# pec.net
KiCad netlist of a schematic drawn in Altium Designer
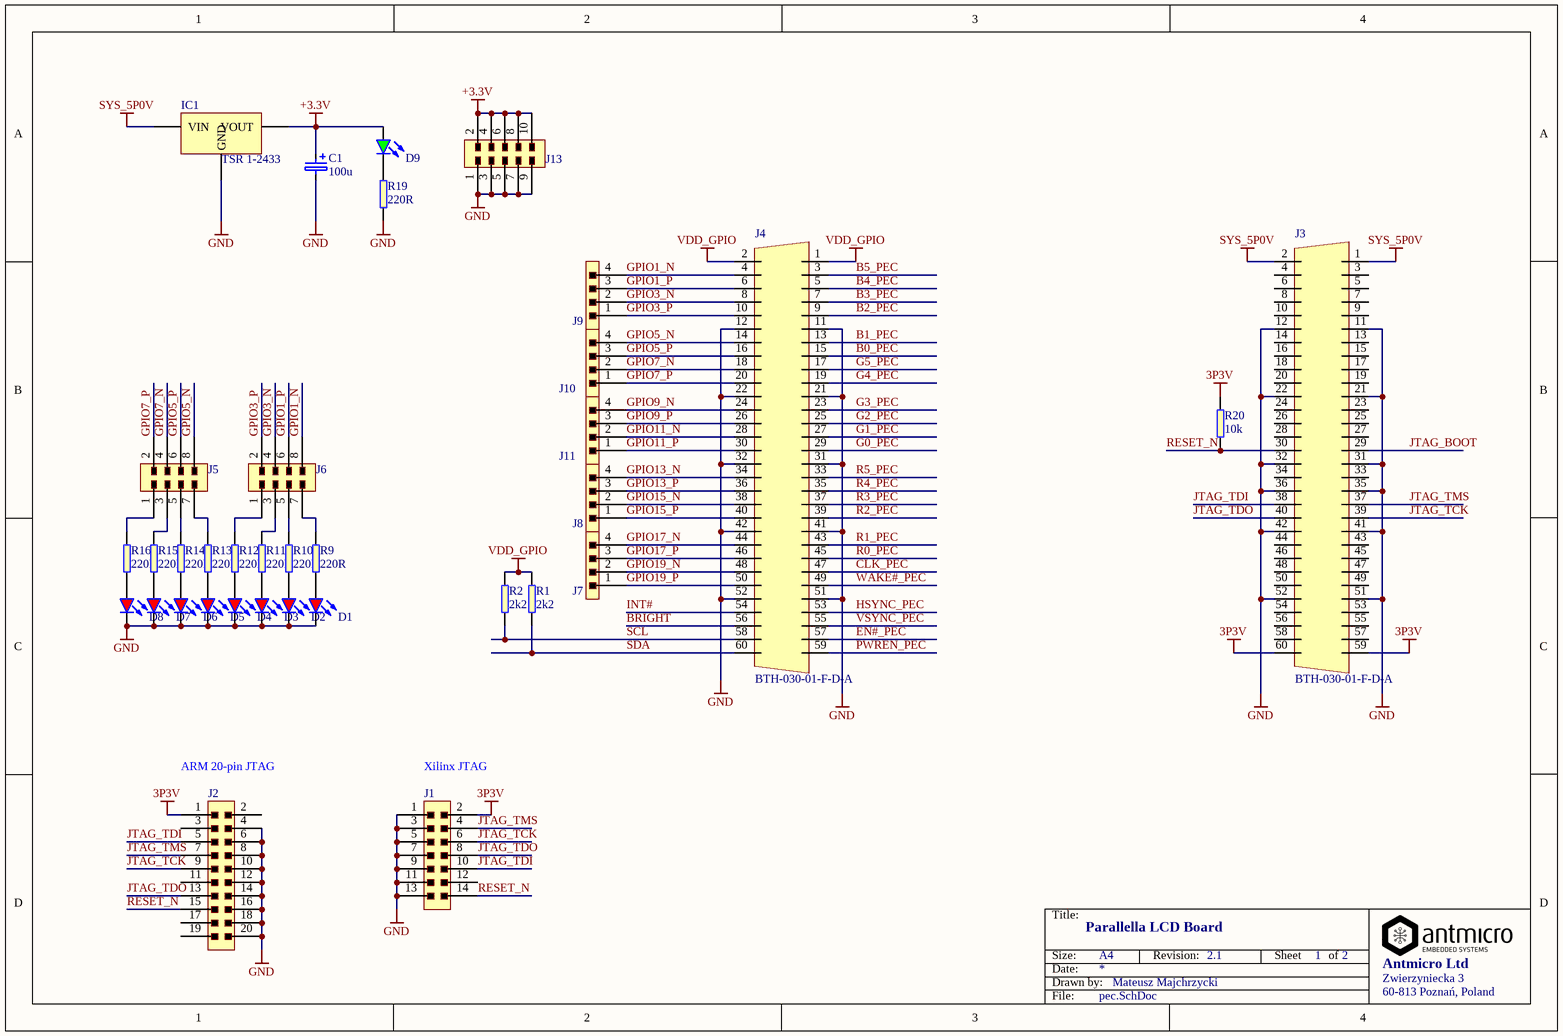
[diagram p0: pec.SchDoc]

(export (version "E")
  (design (tool "Eeschema 10.0.6"))
  (components
    (comp (ref "C1")
      (value "100u")
      (footprint "KEMET_C")
      (description "Tantalum SMT Capacitor 100uF Case KEMET_C")
      (fields (field (name "PART NUMBER") "C_100u_KEMET_C") (field (name "VOLTAGE") "10V"))
      (libsource (lib "AntmicroComponents") (part "CPol"))
    )
    (comp (ref "D1")
      (value "Red")
      (footprint "LED0603")
      (description "LED Red 0603 case")
      (fields (field (name "PART NUMBER") "LED_R"))
      (libsource (lib "AntmicroComponents") (part "LED"))
    )
    (comp (ref "D2")
      (value "Red")
      (footprint "LED0603")
      (description "LED Red 0603 case")
      (fields (field (name "PART NUMBER") "LED_R"))
      (libsource (lib "AntmicroComponents") (part "LED"))
    )
    (comp (ref "D3")
      (value "Red")
      (footprint "LED0603")
      (description "LED Red 0603 case")
      (fields (field (name "PART NUMBER") "LED_R"))
      (libsource (lib "AntmicroComponents") (part "LED"))
    )
    (comp (ref "D4")
      (value "Red")
      (footprint "LED0603")
      (description "LED Red 0603 case")
      (fields (field (name "PART NUMBER") "LED_R"))
      (libsource (lib "AntmicroComponents") (part "LED"))
    )
    (comp (ref "D5")
      (value "Red")
      (footprint "LED0603")
      (description "LED Red 0603 case")
      (fields (field (name "PART NUMBER") "LED_R"))
      (libsource (lib "AntmicroComponents") (part "LED"))
    )
    (comp (ref "D6")
      (value "Red")
      (footprint "LED0603")
      (description "LED Red 0603 case")
      (fields (field (name "PART NUMBER") "LED_R"))
      (libsource (lib "AntmicroComponents") (part "LED"))
    )
    (comp (ref "D7")
      (value "Red")
      (footprint "LED0603")
      (description "LED Red 0603 case")
      (fields (field (name "PART NUMBER") "LED_R"))
      (libsource (lib "AntmicroComponents") (part "LED"))
    )
    (comp (ref "D8")
      (value "Red")
      (footprint "LED0603")
      (description "LED Red 0603 case")
      (fields (field (name "PART NUMBER") "LED_R"))
      (libsource (lib "AntmicroComponents") (part "LED"))
    )
    (comp (ref "D9")
      (value "Green")
      (footprint "LED0603")
      (description "LED Green 0603 case")
      (fields (field (name "PART NUMBER") "LED_G"))
      (libsource (lib "AntmicroComponents") (part "LED"))
    )
    (comp (ref "IC1")
      (value "TSR 1-2433")
      (footprint "TSR1")
      (description "TRACOPOWER - TSR 1-2433 - CONVERTER, DC TO DC, 3.3V, 1A, SIP")
      (libsource (lib "AntmicroComponents") (part "VREG"))
    )
    (comp (ref "J1")
      (value "Molex-87831-1420")
      (footprint "87831-1420")
      (description "2x7 pinhead male")
      (libsource (lib "AntmicroComponents") (part "HEADER_2X7_male"))
    )
    (comp (ref "J2")
      (value "*")
      (footprint "HEADER_2X10_male 2.54mm")
      (description "2x10 pinhead male")
      (fields (field (name "PART NUMBER") "HEADER_2X10_male"))
      (libsource (lib "AntmicroComponents") (part "HEADER_2X10_male"))
    )
    (comp (ref "J3")
      (value "BTH-030-01-F-D-A")
      (footprint "BTH-030-01-F-D-A")
      (libsource (lib "AntmicroComponents") (part "BTH-030-01-F-D-A"))
    )
    (comp (ref "J4")
      (value "BTH-030-01-F-D-A")
      (footprint "BTH-030-01-F-D-A")
      (libsource (lib "AntmicroComponents") (part "BTH-030-01-F-D-A"))
    )
    (comp (ref "J5")
      (value "*")
      (footprint "HEADER_2X4_male 2mm")
      (description "2x4 pinhead male")
      (fields (field (name "PART NUMBER") "HEADER_2X4_male"))
      (libsource (lib "AntmicroComponents") (part "HEADER_2X4_male"))
    )
    (comp (ref "J6")
      (value "*")
      (footprint "HEADER_2X4_male 2mm")
      (description "2x4 pinhead male")
      (fields (field (name "PART NUMBER") "HEADER_2X4_male"))
      (libsource (lib "AntmicroComponents") (part "HEADER_2X4_male"))
    )
    (comp (ref "J7")
      (value "HEADER_1X4_male")
      (footprint "HEADER_1X4_male 2.54mm")
      (description "1x4 pinhead male")
      (libsource (lib "AntmicroComponents") (part "HEADER_1X4_male"))
    )
    (comp (ref "J8")
      (value "HEADER_1X4_male")
      (footprint "HEADER_1X4_male 2.54mm")
      (description "1x4 pinhead male")
      (libsource (lib "AntmicroComponents") (part "HEADER_1X4_male"))
    )
    (comp (ref "J9")
      (value "HEADER_1X4_male")
      (footprint "HEADER_1X4_male 2.54mm")
      (description "1x4 pinhead male")
      (libsource (lib "AntmicroComponents") (part "HEADER_1X4_male"))
    )
    (comp (ref "J10")
      (value "HEADER_1X4_male")
      (footprint "HEADER_1X4_male 2.54mm")
      (description "1x4 pinhead male")
      (libsource (lib "AntmicroComponents") (part "HEADER_1X4_male"))
    )
    (comp (ref "J11")
      (value "HEADER_1X4_male")
      (footprint "HEADER_1X4_male 2.54mm")
      (description "1x4 pinhead male")
      (libsource (lib "AntmicroComponents") (part "HEADER_1X4_male"))
    )
    (comp (ref "J13")
      (value "*")
      (footprint "HEADER_2X5_male 2.54mm")
      (description "2x5 pinhead male")
      (fields (field (name "PART NUMBER") "HEADER_2X5_male"))
      (libsource (lib "AntmicroComponents") (part "HEADER_2X5_male"))
    )
    (comp (ref "R1")
      (value "2k2")
      (footprint "0603")
      (description "SMT Resistor 2k2 0603")
      (fields (field (name "PART NUMBER") "R_2k2_0603"))
      (libsource (lib "") (part "R_1"))
    )
    (comp (ref "R2")
      (value "2k2")
      (footprint "0603")
      (description "SMT Resistor 2k2 0603")
      (fields (field (name "PART NUMBER") "R_2k2_0603"))
      (libsource (lib "") (part "R_1"))
    )
    (comp (ref "R9")
      (value "220R")
      (footprint "0603")
      (description "SMT Resistor 220R 0603")
      (fields (field (name "PART NUMBER") "R_220R_0603"))
      (libsource (lib "AntmicroComponents") (part "R"))
    )
    (comp (ref "R10")
      (value "220R")
      (footprint "0603")
      (description "SMT Resistor 220R 0603")
      (fields (field (name "PART NUMBER") "R_220R_0603"))
      (libsource (lib "AntmicroComponents") (part "R"))
    )
    (comp (ref "R11")
      (value "220R")
      (footprint "0603")
      (description "SMT Resistor 220R 0603")
      (fields (field (name "PART NUMBER") "R_220R_0603"))
      (libsource (lib "AntmicroComponents") (part "R"))
    )
    (comp (ref "R12")
      (value "220R")
      (footprint "0603")
      (description "SMT Resistor 220R 0603")
      (fields (field (name "PART NUMBER") "R_220R_0603"))
      (libsource (lib "AntmicroComponents") (part "R"))
    )
    (comp (ref "R13")
      (value "220R")
      (footprint "0603")
      (description "SMT Resistor 220R 0603")
      (fields (field (name "PART NUMBER") "R_220R_0603"))
      (libsource (lib "AntmicroComponents") (part "R"))
    )
    (comp (ref "R14")
      (value "220R")
      (footprint "0603")
      (description "SMT Resistor 220R 0603")
      (fields (field (name "PART NUMBER") "R_220R_0603"))
      (libsource (lib "AntmicroComponents") (part "R"))
    )
    (comp (ref "R15")
      (value "220R")
      (footprint "0603")
      (description "SMT Resistor 220R 0603")
      (fields (field (name "PART NUMBER") "R_220R_0603"))
      (libsource (lib "AntmicroComponents") (part "R"))
    )
    (comp (ref "R16")
      (value "220R")
      (footprint "0603")
      (description "SMT Resistor 220R 0603")
      (fields (field (name "PART NUMBER") "R_220R_0603"))
      (libsource (lib "AntmicroComponents") (part "R"))
    )
    (comp (ref "R19")
      (value "220R")
      (footprint "0603")
      (description "SMT Resistor 220R 0603")
      (fields (field (name "PART NUMBER") "R_220R_0603"))
      (libsource (lib "AntmicroComponents") (part "R"))
    )
    (comp (ref "R20")
      (value "10k")
      (footprint "0603")
      (description "SMT Resistor 10k 0603")
      (fields (field (name "PART NUMBER") "R_10k_0603"))
      (libsource (lib "AntmicroComponents") (part "R"))
    )
  )
  (nets
    (net (code "1") (name "+3.3V") (class "Default")
      (node (ref "C1") (pin "1") (pinfunction "1_1") (pintype "passive"))
      (node (ref "D9") (pin "A") (pinfunction "A_A") (pintype "passive"))
      (node (ref "IC1") (pin "3") (pinfunction "VOUT_3") (pintype "power_in"))
      (node (ref "J13") (pin "10") (pinfunction "10_10") (pintype "passive"))
      (node (ref "J13") (pin "2") (pinfunction "2_2") (pintype "passive"))
      (node (ref "J13") (pin "4") (pinfunction "4_4") (pintype "passive"))
      (node (ref "J13") (pin "6") (pinfunction "6_6") (pintype "passive"))
      (node (ref "J13") (pin "8") (pinfunction "8_8") (pintype "passive"))
    )
    (net (code "2") (name "/B0_PEC") (class "Default")
      (node (ref "J4") (pin "15") (pinfunction "15_15") (pintype "passive"))
    )
    (net (code "3") (name "/B1_PEC") (class "Default")
      (node (ref "J4") (pin "13") (pinfunction "13_13") (pintype "passive"))
    )
    (net (code "4") (name "/B2_PEC") (class "Default")
      (node (ref "J4") (pin "9") (pinfunction "9_9") (pintype "passive"))
    )
    (net (code "5") (name "/B3_PEC") (class "Default")
      (node (ref "J4") (pin "7") (pinfunction "7_7") (pintype "passive"))
    )
    (net (code "6") (name "/B4_PEC") (class "Default")
      (node (ref "J4") (pin "5") (pinfunction "5_5") (pintype "passive"))
    )
    (net (code "7") (name "/B5_PEC") (class "Default")
      (node (ref "J4") (pin "3") (pinfunction "3_3") (pintype "passive"))
    )
    (net (code "8") (name "/BRIGHT") (class "Default")
      (node (ref "J4") (pin "56") (pinfunction "56_56") (pintype "passive"))
    )
    (net (code "9") (name "/CLK_PEC") (class "Default")
      (node (ref "J4") (pin "47") (pinfunction "47_47") (pintype "passive"))
    )
    (net (code "10") (name "/EN#_PEC") (class "Default")
      (node (ref "J4") (pin "57") (pinfunction "57_57") (pintype "passive"))
    )
    (net (code "11") (name "/G0_PEC") (class "Default")
      (node (ref "J4") (pin "29") (pinfunction "29_29") (pintype "passive"))
    )
    (net (code "12") (name "/G1_PEC") (class "Default")
      (node (ref "J4") (pin "27") (pinfunction "27_27") (pintype "passive"))
    )
    (net (code "13") (name "/G2_PEC") (class "Default")
      (node (ref "J4") (pin "25") (pinfunction "25_25") (pintype "passive"))
    )
    (net (code "14") (name "/G3_PEC") (class "Default")
      (node (ref "J4") (pin "23") (pinfunction "23_23") (pintype "passive"))
    )
    (net (code "15") (name "/G4_PEC") (class "Default")
      (node (ref "J4") (pin "19") (pinfunction "19_19") (pintype "passive"))
    )
    (net (code "16") (name "/G5_PEC") (class "Default")
      (node (ref "J4") (pin "17") (pinfunction "17_17") (pintype "passive"))
    )
    (net (code "17") (name "/GPIO1_N") (class "Default")
      (node (ref "J4") (pin "4") (pinfunction "4_4") (pintype "passive"))
      (node (ref "J6") (pin "8") (pinfunction "8_8") (pintype "passive"))
      (node (ref "J9") (pin "4") (pinfunction "4_4") (pintype "passive"))
    )
    (net (code "18") (name "/GPIO1_P") (class "Default")
      (node (ref "J4") (pin "6") (pinfunction "6_6") (pintype "passive"))
      (node (ref "J6") (pin "6") (pinfunction "6_6") (pintype "passive"))
      (node (ref "J9") (pin "3") (pinfunction "3_3") (pintype "passive"))
    )
    (net (code "19") (name "/GPIO3_N") (class "Default")
      (node (ref "J4") (pin "8") (pinfunction "8_8") (pintype "passive"))
      (node (ref "J6") (pin "4") (pinfunction "4_4") (pintype "passive"))
      (node (ref "J9") (pin "2") (pinfunction "2_2") (pintype "passive"))
    )
    (net (code "20") (name "/GPIO3_P") (class "Default")
      (node (ref "J4") (pin "10") (pinfunction "10_10") (pintype "passive"))
      (node (ref "J6") (pin "2") (pinfunction "2_2") (pintype "passive"))
      (node (ref "J9") (pin "1") (pinfunction "1_1") (pintype "passive"))
    )
    (net (code "21") (name "/GPIO5_N") (class "Default")
      (node (ref "J10") (pin "4") (pinfunction "4_4") (pintype "passive"))
      (node (ref "J4") (pin "14") (pinfunction "14_14") (pintype "passive"))
      (node (ref "J5") (pin "8") (pinfunction "8_8") (pintype "passive"))
    )
    (net (code "22") (name "/GPIO5_P") (class "Default")
      (node (ref "J10") (pin "3") (pinfunction "3_3") (pintype "passive"))
      (node (ref "J4") (pin "16") (pinfunction "16_16") (pintype "passive"))
      (node (ref "J5") (pin "6") (pinfunction "6_6") (pintype "passive"))
    )
    (net (code "23") (name "/GPIO7_N") (class "Default")
      (node (ref "J10") (pin "2") (pinfunction "2_2") (pintype "passive"))
      (node (ref "J4") (pin "18") (pinfunction "18_18") (pintype "passive"))
      (node (ref "J5") (pin "4") (pinfunction "4_4") (pintype "passive"))
    )
    (net (code "24") (name "/GPIO7_P") (class "Default")
      (node (ref "J10") (pin "1") (pinfunction "1_1") (pintype "passive"))
      (node (ref "J4") (pin "20") (pinfunction "20_20") (pintype "passive"))
      (node (ref "J5") (pin "2") (pinfunction "2_2") (pintype "passive"))
    )
    (net (code "25") (name "/GPIO9_N") (class "Default")
      (node (ref "J11") (pin "4") (pinfunction "4_4") (pintype "passive"))
      (node (ref "J4") (pin "24") (pinfunction "24_24") (pintype "passive"))
    )
    (net (code "26") (name "/GPIO9_P") (class "Default")
      (node (ref "J11") (pin "3") (pinfunction "3_3") (pintype "passive"))
      (node (ref "J4") (pin "26") (pinfunction "26_26") (pintype "passive"))
    )
    (net (code "27") (name "/GPIO11_N") (class "Default")
      (node (ref "J11") (pin "2") (pinfunction "2_2") (pintype "passive"))
      (node (ref "J4") (pin "28") (pinfunction "28_28") (pintype "passive"))
    )
    (net (code "28") (name "/GPIO11_P") (class "Default")
      (node (ref "J11") (pin "1") (pinfunction "1_1") (pintype "passive"))
      (node (ref "J4") (pin "30") (pinfunction "30_30") (pintype "passive"))
    )
    (net (code "29") (name "/GPIO13_N") (class "Default")
      (node (ref "J4") (pin "34") (pinfunction "34_34") (pintype "passive"))
      (node (ref "J8") (pin "4") (pinfunction "4_4") (pintype "passive"))
    )
    (net (code "30") (name "/GPIO13_P") (class "Default")
      (node (ref "J4") (pin "36") (pinfunction "36_36") (pintype "passive"))
      (node (ref "J8") (pin "3") (pinfunction "3_3") (pintype "passive"))
    )
    (net (code "31") (name "/GPIO15_N") (class "Default")
      (node (ref "J4") (pin "38") (pinfunction "38_38") (pintype "passive"))
      (node (ref "J8") (pin "2") (pinfunction "2_2") (pintype "passive"))
    )
    (net (code "32") (name "/GPIO15_P") (class "Default")
      (node (ref "J4") (pin "40") (pinfunction "40_40") (pintype "passive"))
      (node (ref "J8") (pin "1") (pinfunction "1_1") (pintype "passive"))
    )
    (net (code "33") (name "/GPIO17_N") (class "Default")
      (node (ref "J4") (pin "44") (pinfunction "44_44") (pintype "passive"))
      (node (ref "J7") (pin "4") (pinfunction "4_4") (pintype "passive"))
    )
    (net (code "34") (name "/GPIO17_P") (class "Default")
      (node (ref "J4") (pin "46") (pinfunction "46_46") (pintype "passive"))
      (node (ref "J7") (pin "3") (pinfunction "3_3") (pintype "passive"))
    )
    (net (code "35") (name "/GPIO19_N") (class "Default")
      (node (ref "J4") (pin "48") (pinfunction "48_48") (pintype "passive"))
      (node (ref "J7") (pin "2") (pinfunction "2_2") (pintype "passive"))
    )
    (net (code "36") (name "/GPIO19_P") (class "Default")
      (node (ref "J4") (pin "50") (pinfunction "50_50") (pintype "passive"))
      (node (ref "J7") (pin "1") (pinfunction "1_1") (pintype "passive"))
    )
    (net (code "37") (name "/HSYNC_PEC") (class "Default")
      (node (ref "J4") (pin "53") (pinfunction "53_53") (pintype "passive"))
    )
    (net (code "38") (name "/INT#") (class "Default")
      (node (ref "J4") (pin "54") (pinfunction "54_54") (pintype "passive"))
    )
    (net (code "39") (name "/JTAG_BOOT") (class "Default")
      (node (ref "J3") (pin "29") (pinfunction "29_29") (pintype "passive"))
    )
    (net (code "40") (name "/JTAG_TCK") (class "Default")
      (node (ref "J1") (pin "6") (pinfunction "6_6") (pintype "passive"))
      (node (ref "J2") (pin "9") (pinfunction "9_9") (pintype "passive"))
      (node (ref "J3") (pin "39") (pinfunction "39_39") (pintype "passive"))
    )
    (net (code "41") (name "/JTAG_TDI") (class "Default")
      (node (ref "J1") (pin "10") (pinfunction "10_10") (pintype "passive"))
      (node (ref "J2") (pin "5") (pinfunction "5_5") (pintype "passive"))
      (node (ref "J3") (pin "38") (pinfunction "38_38") (pintype "passive"))
    )
    (net (code "42") (name "/JTAG_TDO") (class "Default")
      (node (ref "J1") (pin "8") (pinfunction "8_8") (pintype "passive"))
      (node (ref "J2") (pin "13") (pinfunction "13_13") (pintype "passive"))
      (node (ref "J3") (pin "40") (pinfunction "40_40") (pintype "passive"))
    )
    (net (code "43") (name "/JTAG_TMS") (class "Default")
      (node (ref "J1") (pin "4") (pinfunction "4_4") (pintype "passive"))
      (node (ref "J2") (pin "7") (pinfunction "7_7") (pintype "passive"))
      (node (ref "J3") (pin "37") (pinfunction "37_37") (pintype "passive"))
    )
    (net (code "44") (name "/PWREN_PEC") (class "Default")
      (node (ref "J4") (pin "59") (pinfunction "59_59") (pintype "passive"))
    )
    (net (code "45") (name "/R0_PEC") (class "Default")
      (node (ref "J4") (pin "45") (pinfunction "45_45") (pintype "passive"))
    )
    (net (code "46") (name "/R1_PEC") (class "Default")
      (node (ref "J4") (pin "43") (pinfunction "43_43") (pintype "passive"))
    )
    (net (code "47") (name "/R2_PEC") (class "Default")
      (node (ref "J4") (pin "39") (pinfunction "39_39") (pintype "passive"))
    )
    (net (code "48") (name "/R3_PEC") (class "Default")
      (node (ref "J4") (pin "37") (pinfunction "37_37") (pintype "passive"))
    )
    (net (code "49") (name "/R4_PEC") (class "Default")
      (node (ref "J4") (pin "35") (pinfunction "35_35") (pintype "passive"))
    )
    (net (code "50") (name "/R5_PEC") (class "Default")
      (node (ref "J4") (pin "33") (pinfunction "33_33") (pintype "passive"))
    )
    (net (code "51") (name "/RESET_N") (class "Default")
      (node (ref "J1") (pin "14") (pinfunction "14_14") (pintype "passive"))
      (node (ref "J2") (pin "15") (pinfunction "15_15") (pintype "passive"))
      (node (ref "J3") (pin "30") (pinfunction "30_30") (pintype "passive"))
      (node (ref "R20") (pin "1") (pintype "passive"))
    )
    (net (code "52") (name "/SCL") (class "Default")
      (node (ref "J4") (pin "58") (pinfunction "58_58") (pintype "passive"))
      (node (ref "R2") (pin "1") (pintype "passive"))
    )
    (net (code "53") (name "/SDA") (class "Default")
      (node (ref "J4") (pin "60") (pinfunction "60_60") (pintype "passive"))
      (node (ref "R1") (pin "1") (pintype "passive"))
    )
    (net (code "54") (name "/VSYNC_PEC") (class "Default")
      (node (ref "J4") (pin "55") (pinfunction "55_55") (pintype "passive"))
    )
    (net (code "55") (name "/WAKE#_PEC") (class "Default")
      (node (ref "J4") (pin "49") (pinfunction "49_49") (pintype "passive"))
    )
    (net (code "56") (name "3P3V") (class "Default")
      (node (ref "J1") (pin "2") (pinfunction "2_2") (pintype "passive"))
      (node (ref "J2") (pin "1") (pinfunction "1_1") (pintype "passive"))
      (node (ref "J3") (pin "59") (pinfunction "59_59") (pintype "passive"))
      (node (ref "J3") (pin "60") (pinfunction "60_60") (pintype "passive"))
      (node (ref "R20") (pin "2") (pintype "passive"))
    )
    (net (code "57") (name "GND") (class "Default")
      (node (ref "C1") (pin "2") (pinfunction "2_2") (pintype "passive"))
      (node (ref "D1") (pin "K") (pinfunction "K_K") (pintype "passive"))
      (node (ref "D2") (pin "K") (pinfunction "K_K") (pintype "passive"))
      (node (ref "D3") (pin "K") (pinfunction "K_K") (pintype "passive"))
      (node (ref "D4") (pin "K") (pinfunction "K_K") (pintype "passive"))
      (node (ref "D5") (pin "K") (pinfunction "K_K") (pintype "passive"))
      (node (ref "D6") (pin "K") (pinfunction "K_K") (pintype "passive"))
      (node (ref "D7") (pin "K") (pinfunction "K_K") (pintype "passive"))
      (node (ref "D8") (pin "K") (pinfunction "K_K") (pintype "passive"))
      (node (ref "IC1") (pin "2") (pinfunction "GND_2") (pintype "power_in"))
      (node (ref "J1") (pin "1") (pinfunction "1_1") (pintype "passive"))
      (node (ref "J1") (pin "11") (pinfunction "11_11") (pintype "passive"))
      (node (ref "J1") (pin "13") (pinfunction "13_13") (pintype "passive"))
      (node (ref "J1") (pin "3") (pinfunction "3_3") (pintype "passive"))
      (node (ref "J1") (pin "5") (pinfunction "5_5") (pintype "passive"))
      (node (ref "J1") (pin "7") (pinfunction "7_7") (pintype "passive"))
      (node (ref "J1") (pin "9") (pinfunction "9_9") (pintype "passive"))
      (node (ref "J13") (pin "1") (pinfunction "1_1") (pintype "passive"))
      (node (ref "J13") (pin "3") (pinfunction "3_3") (pintype "passive"))
      (node (ref "J13") (pin "5") (pinfunction "5_5") (pintype "passive"))
      (node (ref "J13") (pin "7") (pinfunction "7_7") (pintype "passive"))
      (node (ref "J13") (pin "9") (pinfunction "9_9") (pintype "passive"))
      (node (ref "J2") (pin "10") (pinfunction "10_10") (pintype "passive"))
      (node (ref "J2") (pin "12") (pinfunction "12_12") (pintype "passive"))
      (node (ref "J2") (pin "14") (pinfunction "14_14") (pintype "passive"))
      (node (ref "J2") (pin "16") (pinfunction "16_16") (pintype "passive"))
      (node (ref "J2") (pin "18") (pinfunction "18_18") (pintype "passive"))
      (node (ref "J2") (pin "20") (pinfunction "20_20") (pintype "passive"))
      (node (ref "J2") (pin "4") (pinfunction "4_4") (pintype "passive"))
      (node (ref "J2") (pin "6") (pinfunction "6_6") (pintype "passive"))
      (node (ref "J2") (pin "8") (pinfunction "8_8") (pintype "passive"))
      (node (ref "J3") (pin "11") (pinfunction "11_11") (pintype "passive"))
      (node (ref "J3") (pin "12") (pinfunction "12_12") (pintype "passive"))
      (node (ref "J3") (pin "21") (pinfunction "21_21") (pintype "passive"))
      (node (ref "J3") (pin "22") (pinfunction "22_22") (pintype "passive"))
      (node (ref "J3") (pin "31") (pinfunction "31_31") (pintype "passive"))
      (node (ref "J3") (pin "32") (pinfunction "32_32") (pintype "passive"))
      (node (ref "J3") (pin "35") (pinfunction "35_35") (pintype "passive"))
      (node (ref "J3") (pin "36") (pinfunction "36_36") (pintype "passive"))
      (node (ref "J3") (pin "41") (pinfunction "41_41") (pintype "passive"))
      (node (ref "J3") (pin "42") (pinfunction "42_42") (pintype "passive"))
      (node (ref "J3") (pin "51") (pinfunction "51_51") (pintype "passive"))
      (node (ref "J3") (pin "52") (pinfunction "52_52") (pintype "passive"))
      (node (ref "J4") (pin "11") (pinfunction "11_11") (pintype "passive"))
      (node (ref "J4") (pin "12") (pinfunction "12_12") (pintype "passive"))
      (node (ref "J4") (pin "21") (pinfunction "21_21") (pintype "passive"))
      (node (ref "J4") (pin "22") (pinfunction "22_22") (pintype "passive"))
      (node (ref "J4") (pin "31") (pinfunction "31_31") (pintype "passive"))
      (node (ref "J4") (pin "32") (pinfunction "32_32") (pintype "passive"))
      (node (ref "J4") (pin "41") (pinfunction "41_41") (pintype "passive"))
      (node (ref "J4") (pin "42") (pinfunction "42_42") (pintype "passive"))
      (node (ref "J4") (pin "51") (pinfunction "51_51") (pintype "passive"))
      (node (ref "J4") (pin "52") (pinfunction "52_52") (pintype "passive"))
      (node (ref "R19") (pin "1") (pintype "passive"))
    )
    (net (code "58") (name "Net-(D1-PadA)") (class "Default")
      (node (ref "D1") (pin "A") (pinfunction "A_A") (pintype "passive"))
      (node (ref "R9") (pin "1") (pintype "passive"))
    )
    (net (code "59") (name "Net-(D2-PadA)") (class "Default")
      (node (ref "D2") (pin "A") (pinfunction "A_A") (pintype "passive"))
      (node (ref "R10") (pin "1") (pintype "passive"))
    )
    (net (code "60") (name "Net-(D3-PadA)") (class "Default")
      (node (ref "D3") (pin "A") (pinfunction "A_A") (pintype "passive"))
      (node (ref "R11") (pin "1") (pintype "passive"))
    )
    (net (code "61") (name "Net-(D4-PadA)") (class "Default")
      (node (ref "D4") (pin "A") (pinfunction "A_A") (pintype "passive"))
      (node (ref "R12") (pin "1") (pintype "passive"))
    )
    (net (code "62") (name "Net-(D5-PadA)") (class "Default")
      (node (ref "D5") (pin "A") (pinfunction "A_A") (pintype "passive"))
      (node (ref "R13") (pin "1") (pintype "passive"))
    )
    (net (code "63") (name "Net-(D6-PadA)") (class "Default")
      (node (ref "D6") (pin "A") (pinfunction "A_A") (pintype "passive"))
      (node (ref "R14") (pin "1") (pintype "passive"))
    )
    (net (code "64") (name "Net-(D7-PadA)") (class "Default")
      (node (ref "D7") (pin "A") (pinfunction "A_A") (pintype "passive"))
      (node (ref "R15") (pin "1") (pintype "passive"))
    )
    (net (code "65") (name "Net-(D8-PadA)") (class "Default")
      (node (ref "D8") (pin "A") (pinfunction "A_A") (pintype "passive"))
      (node (ref "R16") (pin "1") (pintype "passive"))
    )
    (net (code "66") (name "Net-(D9-PadK)") (class "Default")
      (node (ref "D9") (pin "K") (pinfunction "K_K") (pintype "passive"))
      (node (ref "R19") (pin "2") (pintype "passive"))
    )
    (net (code "67") (name "Net-(J5-Pad1)") (class "Default")
      (node (ref "J5") (pin "1") (pinfunction "1_1") (pintype "passive"))
      (node (ref "R16") (pin "2") (pintype "passive"))
    )
    (net (code "68") (name "Net-(J5-Pad3)") (class "Default")
      (node (ref "J5") (pin "3") (pinfunction "3_3") (pintype "passive"))
      (node (ref "R15") (pin "2") (pintype "passive"))
    )
    (net (code "69") (name "Net-(J5-Pad5)") (class "Default")
      (node (ref "J5") (pin "5") (pinfunction "5_5") (pintype "passive"))
      (node (ref "R14") (pin "2") (pintype "passive"))
    )
    (net (code "70") (name "Net-(J5-Pad7)") (class "Default")
      (node (ref "J5") (pin "7") (pinfunction "7_7") (pintype "passive"))
      (node (ref "R13") (pin "2") (pintype "passive"))
    )
    (net (code "71") (name "Net-(J6-Pad1)") (class "Default")
      (node (ref "J6") (pin "1") (pinfunction "1_1") (pintype "passive"))
      (node (ref "R12") (pin "2") (pintype "passive"))
    )
    (net (code "72") (name "Net-(J6-Pad3)") (class "Default")
      (node (ref "J6") (pin "3") (pinfunction "3_3") (pintype "passive"))
      (node (ref "R11") (pin "2") (pintype "passive"))
    )
    (net (code "73") (name "Net-(J6-Pad5)") (class "Default")
      (node (ref "J6") (pin "5") (pinfunction "5_5") (pintype "passive"))
      (node (ref "R10") (pin "2") (pintype "passive"))
    )
    (net (code "74") (name "Net-(J6-Pad7)") (class "Default")
      (node (ref "J6") (pin "7") (pinfunction "7_7") (pintype "passive"))
      (node (ref "R9") (pin "2") (pintype "passive"))
    )
    (net (code "75") (name "SYS_5P0V") (class "Default")
      (node (ref "IC1") (pin "1") (pinfunction "VIN_1") (pintype "power_in"))
      (node (ref "J3") (pin "1") (pinfunction "1_1") (pintype "passive"))
      (node (ref "J3") (pin "2") (pinfunction "2_2") (pintype "passive"))
    )
    (net (code "76") (name "VDD_GPIO") (class "Default")
      (node (ref "J4") (pin "1") (pinfunction "1_1") (pintype "passive"))
      (node (ref "J4") (pin "2") (pinfunction "2_2") (pintype "passive"))
      (node (ref "R1") (pin "2") (pintype "passive"))
      (node (ref "R2") (pin "2") (pintype "passive"))
    )
    (net (code "77") (name "unconnected-(J1-Pad12)") (class "Default")
      (node (ref "J1") (pin "12") (pinfunction "12_12") (pintype "passive"))
    )
    (net (code "78") (name "unconnected-(J2-Pad2)") (class "Default")
      (node (ref "J2") (pin "2") (pinfunction "2_2") (pintype "passive"))
    )
    (net (code "79") (name "unconnected-(J2-Pad3)") (class "Default")
      (node (ref "J2") (pin "3") (pinfunction "3_3") (pintype "passive"))
    )
    (net (code "80") (name "unconnected-(J2-Pad11)") (class "Default")
      (node (ref "J2") (pin "11") (pinfunction "11_11") (pintype "passive"))
    )
    (net (code "81") (name "unconnected-(J2-Pad17)") (class "Default")
      (node (ref "J2") (pin "17") (pinfunction "17_17") (pintype "passive"))
    )
    (net (code "82") (name "unconnected-(J2-Pad19)") (class "Default")
      (node (ref "J2") (pin "19") (pinfunction "19_19") (pintype "passive"))
    )
    (net (code "83") (name "unconnected-(J3-Pad3)") (class "Default")
      (node (ref "J3") (pin "3") (pinfunction "3_3") (pintype "passive"))
    )
    (net (code "84") (name "unconnected-(J3-Pad4)") (class "Default")
      (node (ref "J3") (pin "4") (pinfunction "4_4") (pintype "passive"))
    )
    (net (code "85") (name "unconnected-(J3-Pad5)") (class "Default")
      (node (ref "J3") (pin "5") (pinfunction "5_5") (pintype "passive"))
    )
    (net (code "86") (name "unconnected-(J3-Pad6)") (class "Default")
      (node (ref "J3") (pin "6") (pinfunction "6_6") (pintype "passive"))
    )
    (net (code "87") (name "unconnected-(J3-Pad7)") (class "Default")
      (node (ref "J3") (pin "7") (pinfunction "7_7") (pintype "passive"))
    )
    (net (code "88") (name "unconnected-(J3-Pad8)") (class "Default")
      (node (ref "J3") (pin "8") (pinfunction "8_8") (pintype "passive"))
    )
    (net (code "89") (name "unconnected-(J3-Pad9)") (class "Default")
      (node (ref "J3") (pin "9") (pinfunction "9_9") (pintype "passive"))
    )
    (net (code "90") (name "unconnected-(J3-Pad10)") (class "Default")
      (node (ref "J3") (pin "10") (pinfunction "10_10") (pintype "passive"))
    )
    (net (code "91") (name "unconnected-(J3-Pad13)") (class "Default")
      (node (ref "J3") (pin "13") (pinfunction "13_13") (pintype "passive"))
    )
    (net (code "92") (name "unconnected-(J3-Pad14)") (class "Default")
      (node (ref "J3") (pin "14") (pinfunction "14_14") (pintype "passive"))
    )
    (net (code "93") (name "unconnected-(J3-Pad15)") (class "Default")
      (node (ref "J3") (pin "15") (pinfunction "15_15") (pintype "passive"))
    )
    (net (code "94") (name "unconnected-(J3-Pad16)") (class "Default")
      (node (ref "J3") (pin "16") (pinfunction "16_16") (pintype "passive"))
    )
    (net (code "95") (name "unconnected-(J3-Pad17)") (class "Default")
      (node (ref "J3") (pin "17") (pinfunction "17_17") (pintype "passive"))
    )
    (net (code "96") (name "unconnected-(J3-Pad18)") (class "Default")
      (node (ref "J3") (pin "18") (pinfunction "18_18") (pintype "passive"))
    )
    (net (code "97") (name "unconnected-(J3-Pad19)") (class "Default")
      (node (ref "J3") (pin "19") (pinfunction "19_19") (pintype "passive"))
    )
    (net (code "98") (name "unconnected-(J3-Pad20)") (class "Default")
      (node (ref "J3") (pin "20") (pinfunction "20_20") (pintype "passive"))
    )
    (net (code "99") (name "unconnected-(J3-Pad23)") (class "Default")
      (node (ref "J3") (pin "23") (pinfunction "23_23") (pintype "passive"))
    )
    (net (code "100") (name "unconnected-(J3-Pad24)") (class "Default")
      (node (ref "J3") (pin "24") (pinfunction "24_24") (pintype "passive"))
    )
    (net (code "101") (name "unconnected-(J3-Pad25)") (class "Default")
      (node (ref "J3") (pin "25") (pinfunction "25_25") (pintype "passive"))
    )
    (net (code "102") (name "unconnected-(J3-Pad26)") (class "Default")
      (node (ref "J3") (pin "26") (pinfunction "26_26") (pintype "passive"))
    )
    (net (code "103") (name "unconnected-(J3-Pad27)") (class "Default")
      (node (ref "J3") (pin "27") (pinfunction "27_27") (pintype "passive"))
    )
    (net (code "104") (name "unconnected-(J3-Pad28)") (class "Default")
      (node (ref "J3") (pin "28") (pinfunction "28_28") (pintype "passive"))
    )
    (net (code "105") (name "unconnected-(J3-Pad33)") (class "Default")
      (node (ref "J3") (pin "33") (pinfunction "33_33") (pintype "passive"))
    )
    (net (code "106") (name "unconnected-(J3-Pad34)") (class "Default")
      (node (ref "J3") (pin "34") (pinfunction "34_34") (pintype "passive"))
    )
    (net (code "107") (name "unconnected-(J3-Pad43)") (class "Default")
      (node (ref "J3") (pin "43") (pinfunction "43_43") (pintype "passive"))
    )
    (net (code "108") (name "unconnected-(J3-Pad44)") (class "Default")
      (node (ref "J3") (pin "44") (pinfunction "44_44") (pintype "passive"))
    )
    (net (code "109") (name "unconnected-(J3-Pad45)") (class "Default")
      (node (ref "J3") (pin "45") (pinfunction "45_45") (pintype "passive"))
    )
    (net (code "110") (name "unconnected-(J3-Pad46)") (class "Default")
      (node (ref "J3") (pin "46") (pinfunction "46_46") (pintype "passive"))
    )
    (net (code "111") (name "unconnected-(J3-Pad47)") (class "Default")
      (node (ref "J3") (pin "47") (pinfunction "47_47") (pintype "passive"))
    )
    (net (code "112") (name "unconnected-(J3-Pad48)") (class "Default")
      (node (ref "J3") (pin "48") (pinfunction "48_48") (pintype "passive"))
    )
    (net (code "113") (name "unconnected-(J3-Pad49)") (class "Default")
      (node (ref "J3") (pin "49") (pinfunction "49_49") (pintype "passive"))
    )
    (net (code "114") (name "unconnected-(J3-Pad50)") (class "Default")
      (node (ref "J3") (pin "50") (pinfunction "50_50") (pintype "passive"))
    )
    (net (code "115") (name "unconnected-(J3-Pad53)") (class "Default")
      (node (ref "J3") (pin "53") (pinfunction "53_53") (pintype "passive"))
    )
    (net (code "116") (name "unconnected-(J3-Pad54)") (class "Default")
      (node (ref "J3") (pin "54") (pinfunction "54_54") (pintype "passive"))
    )
    (net (code "117") (name "unconnected-(J3-Pad55)") (class "Default")
      (node (ref "J3") (pin "55") (pinfunction "55_55") (pintype "passive"))
    )
    (net (code "118") (name "unconnected-(J3-Pad56)") (class "Default")
      (node (ref "J3") (pin "56") (pinfunction "56_56") (pintype "passive"))
    )
    (net (code "119") (name "unconnected-(J3-Pad57)") (class "Default")
      (node (ref "J3") (pin "57") (pinfunction "57_57") (pintype "passive"))
    )
    (net (code "120") (name "unconnected-(J3-Pad58)") (class "Default")
      (node (ref "J3") (pin "58") (pinfunction "58_58") (pintype "passive"))
    )
  )
)
